# THT_Dual_GNSS_IMU_GSM_Rooftop_Unit_for_A.net
KiCad netlist of a schematic drawn in EasyEDA
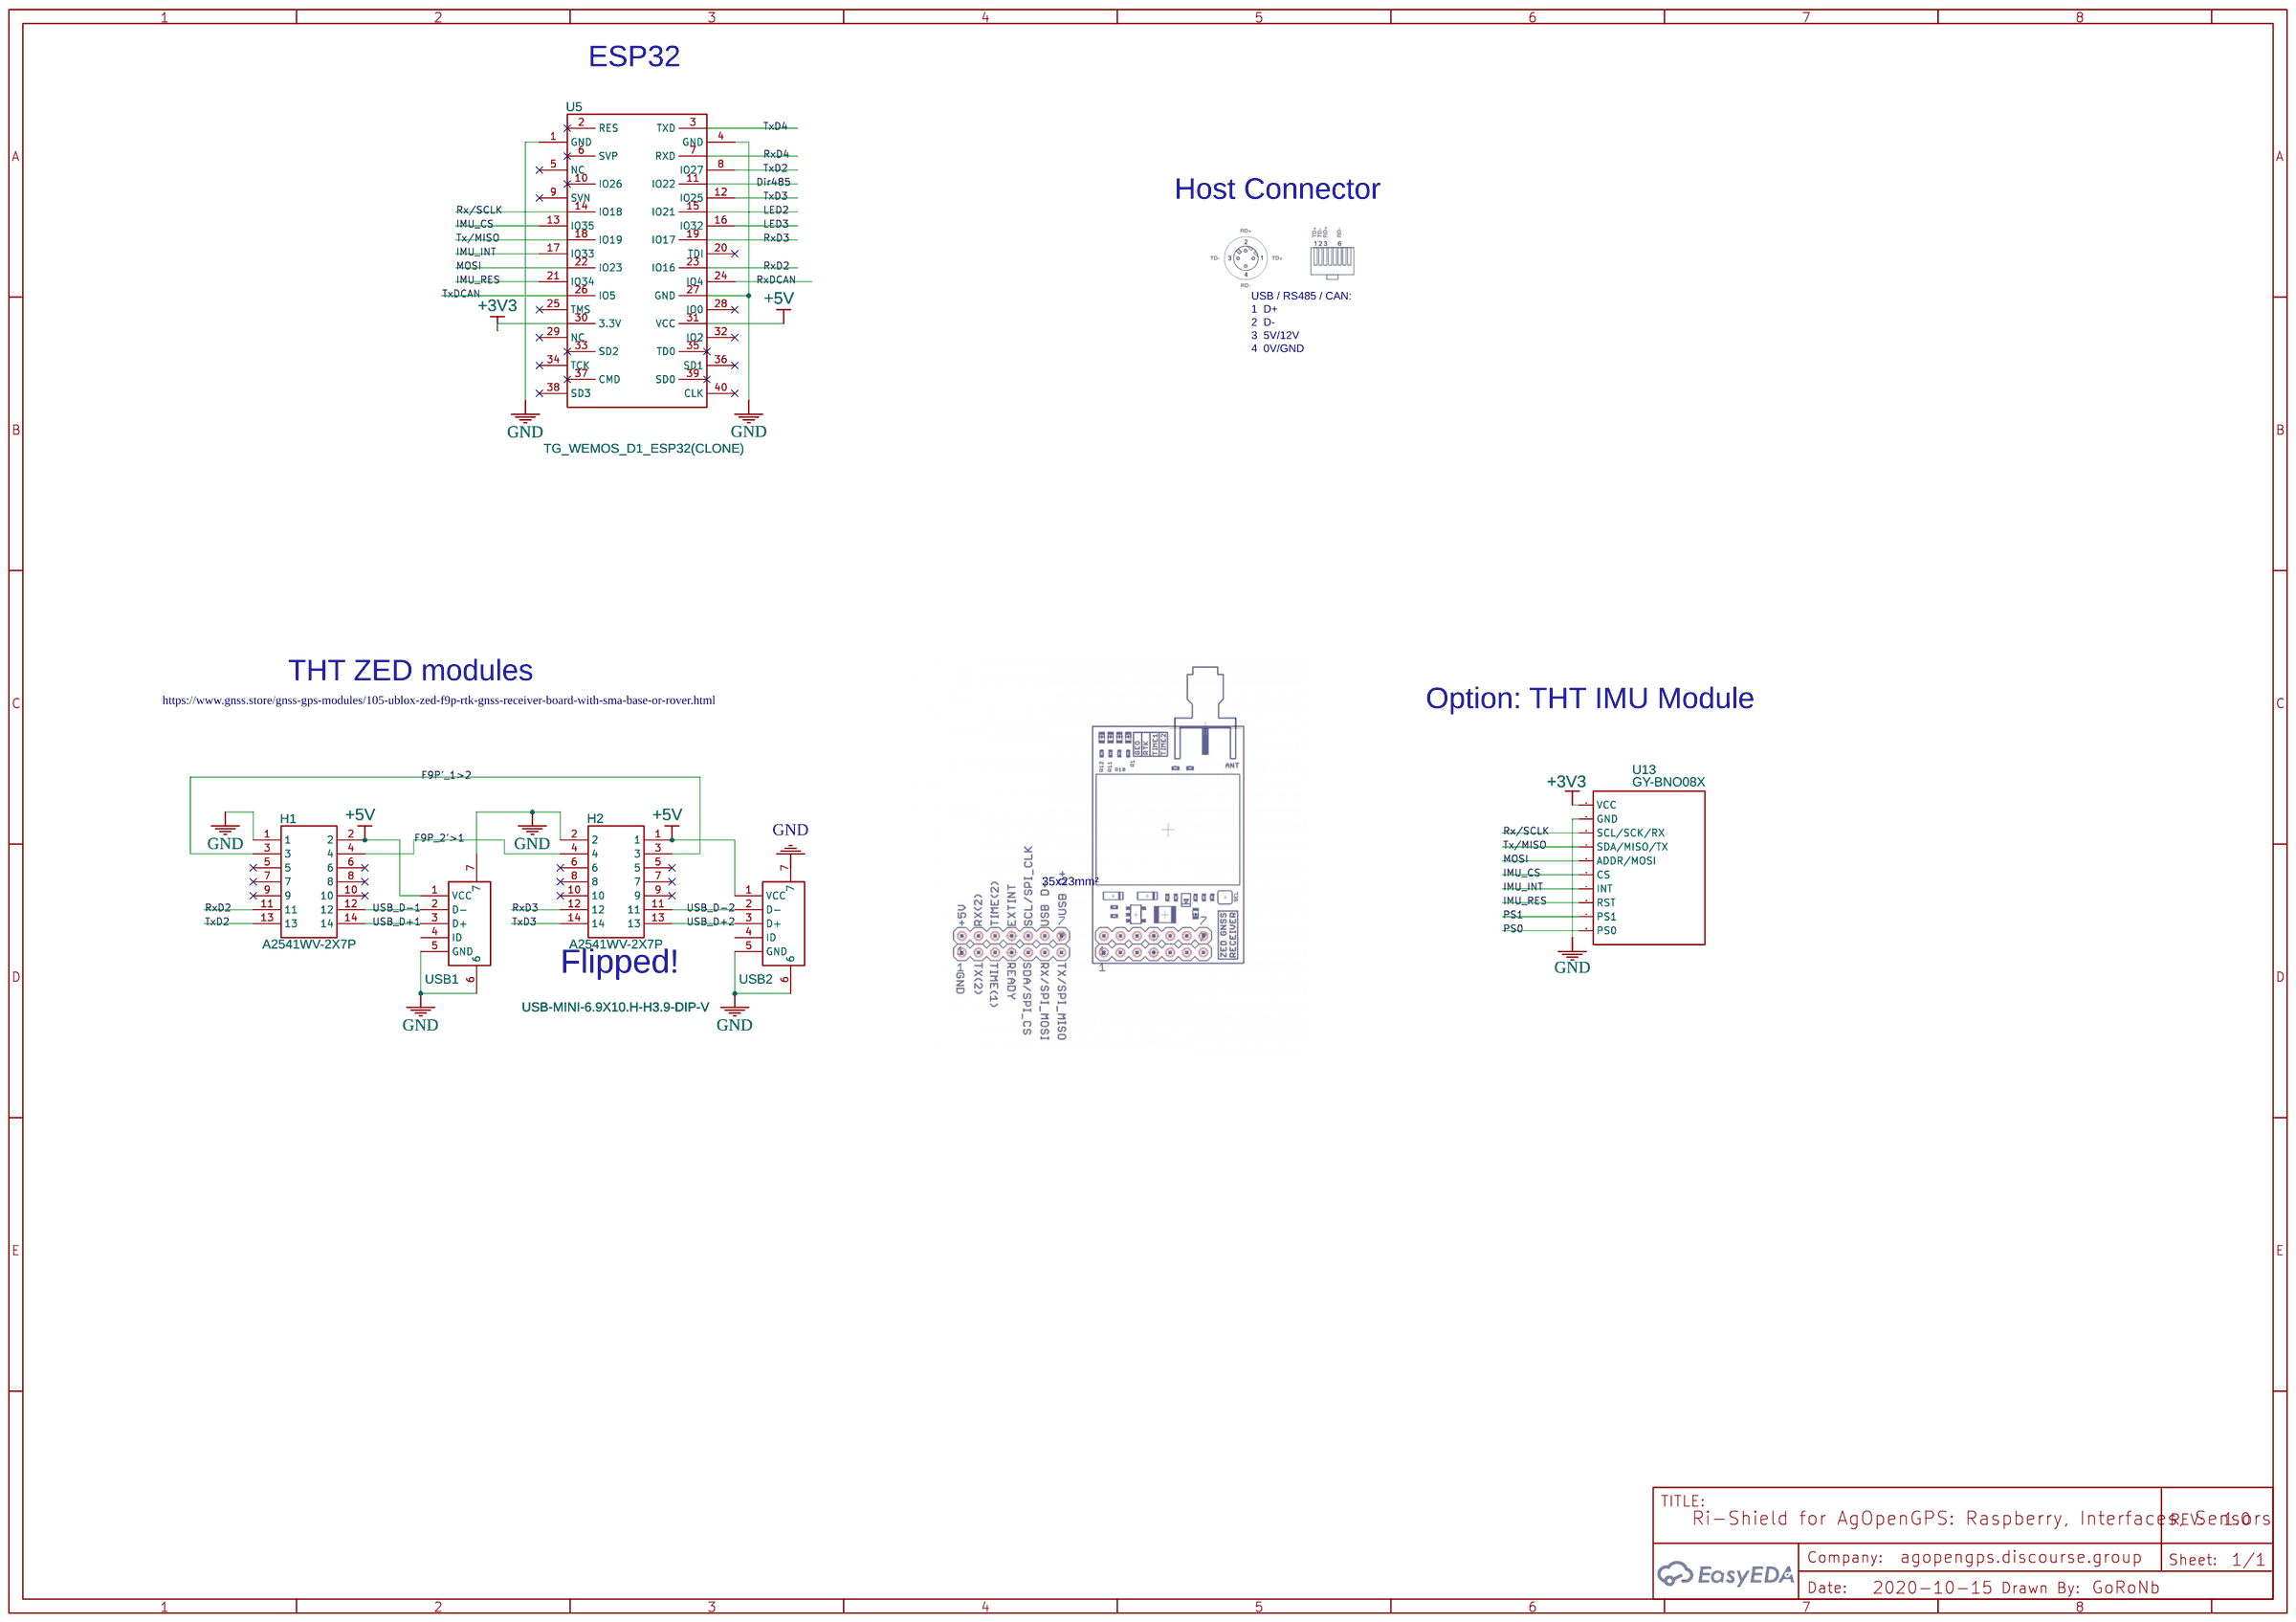
[diagram p0: schematic sheet]

(export (version "E")
  (design (tool "Eeschema 10.0.6"))
  (components
    (comp (ref "H1")
      (value "A2541WV-2X7P")
      (fields
        (field (name "BOM_Manufacturer Part") "A2541WV-2x7P")
        (field (name "BOM_Supplier Part") "C225522")
      )
      (libsource (lib "") (part "A2541WV-2X7P"))
    )
    (comp (ref "H2")
      (value "A2541WV-2X7P")
      (fields
        (field (name "BOM_Manufacturer Part") "A2541WV-2x7P")
        (field (name "BOM_Supplier Part") "C225522")
      )
      (libsource (lib "") (part "A2541WV-2X7P_1"))
    )
    (comp (ref "U5")
      (value "TG_WEMOS_D1_ESP32(CLONE)")
      (fields
        (field (name "BOM_Manufacturer Part") "New SchematicLib")
        (field (name "BOM_Supplier Part") "undefined")
      )
      (libsource (lib "") (part "TG_WEMOS_D1_ESP32(CLONE)"))
    )
    (comp (ref "U13") (value "GY-BNO08X") (libsource (lib "") (part "GY-BNO08X")))
    (comp (ref "USB1")
      (value "USB-MINI-6.9X10.H-H3.9-DIP-V")
      (fields (field (name "BOM_Supplier Part") "C13453"))
      (libsource (lib "") (part "USB-MINI-6.9X10.H-H3.9-DIP-V"))
    )
    (comp (ref "USB2")
      (value "USB-MINI-6.9X10.H-H3.9-DIP-V")
      (fields (field (name "BOM_Supplier Part") "C13453"))
      (libsource (lib "") (part "USB-MINI-6.9X10.H-H3.9-DIP-V"))
    )
  )
  (nets
    (net (code "1") (name "+3V3") (class "Default")
      (node (ref "U13") (pin "1") (pinfunction "VCC_1") (pintype "input"))
      (node (ref "U5") (pin "30") (pinfunction "3.3V_30") (pintype "unspecified"))
    )
    (net (code "2") (name "+5V") (class "Default")
      (node (ref "H1") (pin "2") (pinfunction "2_2") (pintype "unspecified"))
      (node (ref "H2") (pin "1") (pinfunction "1_1") (pintype "unspecified"))
      (node (ref "U5") (pin "31") (pinfunction "VCC_31") (pintype "unspecified"))
      (node (ref "USB1") (pin "1") (pinfunction "VCC_1") (pintype "unspecified"))
      (node (ref "USB2") (pin "1") (pinfunction "VCC_1") (pintype "unspecified"))
    )
    (net (code "3") (name "/Dir485") (class "Default")
      (node (ref "U5") (pin "11") (pinfunction "IO22_11") (pintype "unspecified"))
    )
    (net (code "4") (name "/F9P'_1>2") (class "Default")
      (node (ref "H1") (pin "3") (pinfunction "3_3") (pintype "unspecified"))
      (node (ref "H2") (pin "3") (pinfunction "3_3") (pintype "unspecified"))
    )
    (net (code "5") (name "/F9P_2'>1") (class "Default")
      (node (ref "H1") (pin "4") (pinfunction "4_4") (pintype "unspecified"))
      (node (ref "H2") (pin "4") (pinfunction "4_4") (pintype "unspecified"))
    )
    (net (code "6") (name "/IMU_CS") (class "Default")
      (node (ref "U13") (pin "6") (pinfunction "CS_6") (pintype "input"))
      (node (ref "U5") (pin "13") (pinfunction "IO35_13") (pintype "unspecified"))
    )
    (net (code "7") (name "/IMU_INT") (class "Default")
      (node (ref "U13") (pin "7") (pinfunction "INT_7") (pintype "input"))
      (node (ref "U5") (pin "17") (pinfunction "IO33_17") (pintype "unspecified"))
    )
    (net (code "8") (name "/IMU_RES") (class "Default")
      (node (ref "U13") (pin "8") (pinfunction "RST_8") (pintype "input"))
      (node (ref "U5") (pin "21") (pinfunction "IO34_21") (pintype "unspecified"))
    )
    (net (code "9") (name "/LED2") (class "Default")
      (node (ref "U5") (pin "15") (pinfunction "IO21_15") (pintype "unspecified"))
    )
    (net (code "10") (name "/LED3") (class "Default")
      (node (ref "U5") (pin "16") (pinfunction "IO32_16") (pintype "unspecified"))
    )
    (net (code "11") (name "/MOSI") (class "Default")
      (node (ref "U13") (pin "5") (pinfunction "ADDR/MOSI_5") (pintype "input"))
      (node (ref "U5") (pin "22") (pinfunction "IO23_22") (pintype "unspecified"))
    )
    (net (code "12") (name "/PS0") (class "Default")
      (node (ref "U13") (pin "10") (pinfunction "PS0_10") (pintype "input"))
    )
    (net (code "13") (name "/PS1") (class "Default")
      (node (ref "U13") (pin "9") (pinfunction "PS1_9") (pintype "input"))
    )
    (net (code "14") (name "/RxD2") (class "Default")
      (node (ref "H1") (pin "11") (pinfunction "11_11") (pintype "unspecified"))
      (node (ref "U5") (pin "23") (pinfunction "IO16_23") (pintype "unspecified"))
    )
    (net (code "15") (name "/RxD3") (class "Default")
      (node (ref "H2") (pin "12") (pinfunction "12_12") (pintype "unspecified"))
      (node (ref "U5") (pin "19") (pinfunction "IO17_19") (pintype "unspecified"))
    )
    (net (code "16") (name "/RxD4") (class "Default")
      (node (ref "U5") (pin "7") (pinfunction "RXD_7") (pintype "unspecified"))
    )
    (net (code "17") (name "/RxDCAN") (class "Default")
      (node (ref "U5") (pin "24") (pinfunction "IO4_24") (pintype "unspecified"))
    )
    (net (code "18") (name "/Rx{slash}SCLK") (class "Default")
      (node (ref "U13") (pin "3") (pinfunction "SCL/SCK/RX_3") (pintype "input"))
      (node (ref "U5") (pin "14") (pinfunction "IO18_14") (pintype "unspecified"))
    )
    (net (code "19") (name "/TxD2") (class "Default")
      (node (ref "H1") (pin "13") (pinfunction "13_13") (pintype "unspecified"))
      (node (ref "U5") (pin "8") (pinfunction "IO27_8") (pintype "unspecified"))
    )
    (net (code "20") (name "/TxD3") (class "Default")
      (node (ref "H2") (pin "14") (pinfunction "14_14") (pintype "unspecified"))
      (node (ref "U5") (pin "12") (pinfunction "IO25_12") (pintype "unspecified"))
    )
    (net (code "21") (name "/TxD4") (class "Default")
      (node (ref "U5") (pin "3") (pinfunction "TXD_3") (pintype "unspecified"))
    )
    (net (code "22") (name "/TxDCAN") (class "Default")
      (node (ref "U5") (pin "26") (pinfunction "IO5_26") (pintype "unspecified"))
    )
    (net (code "23") (name "/Tx{slash}MISO") (class "Default")
      (node (ref "U13") (pin "4") (pinfunction "SDA/MISO/TX_4") (pintype "input"))
      (node (ref "U5") (pin "18") (pinfunction "IO19_18") (pintype "unspecified"))
    )
    (net (code "24") (name "/USB_D+1") (class "Default")
      (node (ref "H1") (pin "14") (pinfunction "14_14") (pintype "unspecified"))
      (node (ref "USB1") (pin "3") (pinfunction "D+_3") (pintype "unspecified"))
    )
    (net (code "25") (name "/USB_D+2") (class "Default")
      (node (ref "H2") (pin "13") (pinfunction "13_13") (pintype "unspecified"))
      (node (ref "USB2") (pin "3") (pinfunction "D+_3") (pintype "unspecified"))
    )
    (net (code "26") (name "/USB_D-1") (class "Default")
      (node (ref "H1") (pin "12") (pinfunction "12_12") (pintype "unspecified"))
      (node (ref "USB1") (pin "2") (pinfunction "D-_2") (pintype "unspecified"))
    )
    (net (code "27") (name "/USB_D-2") (class "Default")
      (node (ref "H2") (pin "11") (pinfunction "11_11") (pintype "unspecified"))
      (node (ref "USB2") (pin "2") (pinfunction "D-_2") (pintype "unspecified"))
    )
    (net (code "28") (name "GND") (class "Default")
      (node (ref "H1") (pin "1") (pinfunction "1_1") (pintype "unspecified"))
      (node (ref "H2") (pin "2") (pinfunction "2_2") (pintype "unspecified"))
      (node (ref "U13") (pin "2") (pinfunction "GND_2") (pintype "input"))
      (node (ref "U5") (pin "1") (pinfunction "GND_1") (pintype "unspecified"))
      (node (ref "U5") (pin "27") (pinfunction "GND_27") (pintype "unspecified"))
      (node (ref "U5") (pin "4") (pinfunction "GND_4") (pintype "unspecified"))
      (node (ref "USB1") (pin "5") (pinfunction "GND_5") (pintype "unspecified"))
      (node (ref "USB1") (pin "6") (pinfunction "6_6") (pintype "unspecified"))
      (node (ref "USB1") (pin "7") (pinfunction "7_7") (pintype "unspecified"))
      (node (ref "USB2") (pin "5") (pinfunction "GND_5") (pintype "unspecified"))
      (node (ref "USB2") (pin "6") (pinfunction "6_6") (pintype "unspecified"))
      (node (ref "USB2") (pin "7") (pinfunction "7_7") (pintype "unspecified"))
    )
    (net (code "29") (name "unconnected-(H1-Pad5)") (class "Default")
      (node (ref "H1") (pin "5") (pinfunction "5_5") (pintype "unspecified+no_connect"))
    )
    (net (code "30") (name "unconnected-(H1-Pad6)") (class "Default")
      (node (ref "H1") (pin "6") (pinfunction "6_6") (pintype "unspecified+no_connect"))
    )
    (net (code "31") (name "unconnected-(H1-Pad7)") (class "Default")
      (node (ref "H1") (pin "7") (pinfunction "7_7") (pintype "unspecified+no_connect"))
    )
    (net (code "32") (name "unconnected-(H1-Pad8)") (class "Default")
      (node (ref "H1") (pin "8") (pinfunction "8_8") (pintype "unspecified+no_connect"))
    )
    (net (code "33") (name "unconnected-(H1-Pad9)") (class "Default")
      (node (ref "H1") (pin "9") (pinfunction "9_9") (pintype "unspecified+no_connect"))
    )
    (net (code "34") (name "unconnected-(H1-Pad10)") (class "Default")
      (node (ref "H1") (pin "10") (pinfunction "10_10") (pintype "unspecified+no_connect"))
    )
    (net (code "35") (name "unconnected-(H2-Pad5)") (class "Default")
      (node (ref "H2") (pin "5") (pinfunction "5_5") (pintype "unspecified+no_connect"))
    )
    (net (code "36") (name "unconnected-(H2-Pad6)") (class "Default")
      (node (ref "H2") (pin "6") (pinfunction "6_6") (pintype "unspecified+no_connect"))
    )
    (net (code "37") (name "unconnected-(H2-Pad7)") (class "Default")
      (node (ref "H2") (pin "7") (pinfunction "7_7") (pintype "unspecified+no_connect"))
    )
    (net (code "38") (name "unconnected-(H2-Pad8)") (class "Default")
      (node (ref "H2") (pin "8") (pinfunction "8_8") (pintype "unspecified+no_connect"))
    )
    (net (code "39") (name "unconnected-(H2-Pad9)") (class "Default")
      (node (ref "H2") (pin "9") (pinfunction "9_9") (pintype "unspecified+no_connect"))
    )
    (net (code "40") (name "unconnected-(H2-Pad10)") (class "Default")
      (node (ref "H2") (pin "10") (pinfunction "10_10") (pintype "unspecified+no_connect"))
    )
    (net (code "41") (name "unconnected-(U5-CLK-Pad40)") (class "Default")
      (node (ref "U5") (pin "40") (pinfunction "CLK_40") (pintype "unspecified+no_connect"))
    )
    (net (code "42") (name "unconnected-(U5-CMD-Pad37)") (class "Default")
      (node (ref "U5") (pin "37") (pinfunction "CMD_37") (pintype "unspecified+no_connect"))
    )
    (net (code "43") (name "unconnected-(U5-IO0-Pad28)") (class "Default")
      (node (ref "U5") (pin "28") (pinfunction "IO0_28") (pintype "unspecified+no_connect"))
    )
    (net (code "44") (name "unconnected-(U5-IO2-Pad32)") (class "Default")
      (node (ref "U5") (pin "32") (pinfunction "IO2_32") (pintype "unspecified+no_connect"))
    )
    (net (code "45") (name "unconnected-(U5-IO26-Pad10)") (class "Default")
      (node (ref "U5") (pin "10") (pinfunction "IO26_10") (pintype "unspecified+no_connect"))
    )
    (net (code "46") (name "unconnected-(U5-NC-Pad5)") (class "Default")
      (node (ref "U5") (pin "5") (pinfunction "NC_5") (pintype "unspecified+no_connect"))
    )
    (net (code "47") (name "unconnected-(U5-NC-Pad29)") (class "Default")
      (node (ref "U5") (pin "29") (pinfunction "NC_29") (pintype "unspecified+no_connect"))
    )
    (net (code "48") (name "unconnected-(U5-RES-Pad2)") (class "Default")
      (node (ref "U5") (pin "2") (pinfunction "RES_2") (pintype "unspecified+no_connect"))
    )
    (net (code "49") (name "unconnected-(U5-SD0-Pad39)") (class "Default")
      (node (ref "U5") (pin "39") (pinfunction "SD0_39") (pintype "unspecified+no_connect"))
    )
    (net (code "50") (name "unconnected-(U5-SD1-Pad36)") (class "Default")
      (node (ref "U5") (pin "36") (pinfunction "SD1_36") (pintype "unspecified+no_connect"))
    )
    (net (code "51") (name "unconnected-(U5-SD2-Pad33)") (class "Default")
      (node (ref "U5") (pin "33") (pinfunction "SD2_33") (pintype "unspecified+no_connect"))
    )
    (net (code "52") (name "unconnected-(U5-SD3-Pad38)") (class "Default")
      (node (ref "U5") (pin "38") (pinfunction "SD3_38") (pintype "unspecified+no_connect"))
    )
    (net (code "53") (name "unconnected-(U5-SVN-Pad9)") (class "Default")
      (node (ref "U5") (pin "9") (pinfunction "SVN_9") (pintype "unspecified+no_connect"))
    )
    (net (code "54") (name "unconnected-(U5-SVP-Pad6)") (class "Default")
      (node (ref "U5") (pin "6") (pinfunction "SVP_6") (pintype "unspecified+no_connect"))
    )
    (net (code "55") (name "unconnected-(U5-TCK-Pad34)") (class "Default")
      (node (ref "U5") (pin "34") (pinfunction "TCK_34") (pintype "unspecified+no_connect"))
    )
    (net (code "56") (name "unconnected-(U5-TD0-Pad35)") (class "Default")
      (node (ref "U5") (pin "35") (pinfunction "TD0_35") (pintype "unspecified+no_connect"))
    )
    (net (code "57") (name "unconnected-(U5-TDI-Pad20)") (class "Default")
      (node (ref "U5") (pin "20") (pinfunction "TDI_20") (pintype "unspecified+no_connect"))
    )
    (net (code "58") (name "unconnected-(U5-TMS-Pad25)") (class "Default")
      (node (ref "U5") (pin "25") (pinfunction "TMS_25") (pintype "unspecified+no_connect"))
    )
    (net (code "59") (name "unconnected-(USB1-ID-Pad4)") (class "Default")
      (node (ref "USB1") (pin "4") (pinfunction "ID_4") (pintype "unspecified"))
    )
    (net (code "60") (name "unconnected-(USB2-ID-Pad4)") (class "Default")
      (node (ref "USB2") (pin "4") (pinfunction "ID_4") (pintype "unspecified"))
    )
  )
)
